# Airflow.net
KiCad netlist of a schematic drawn in EAGLE
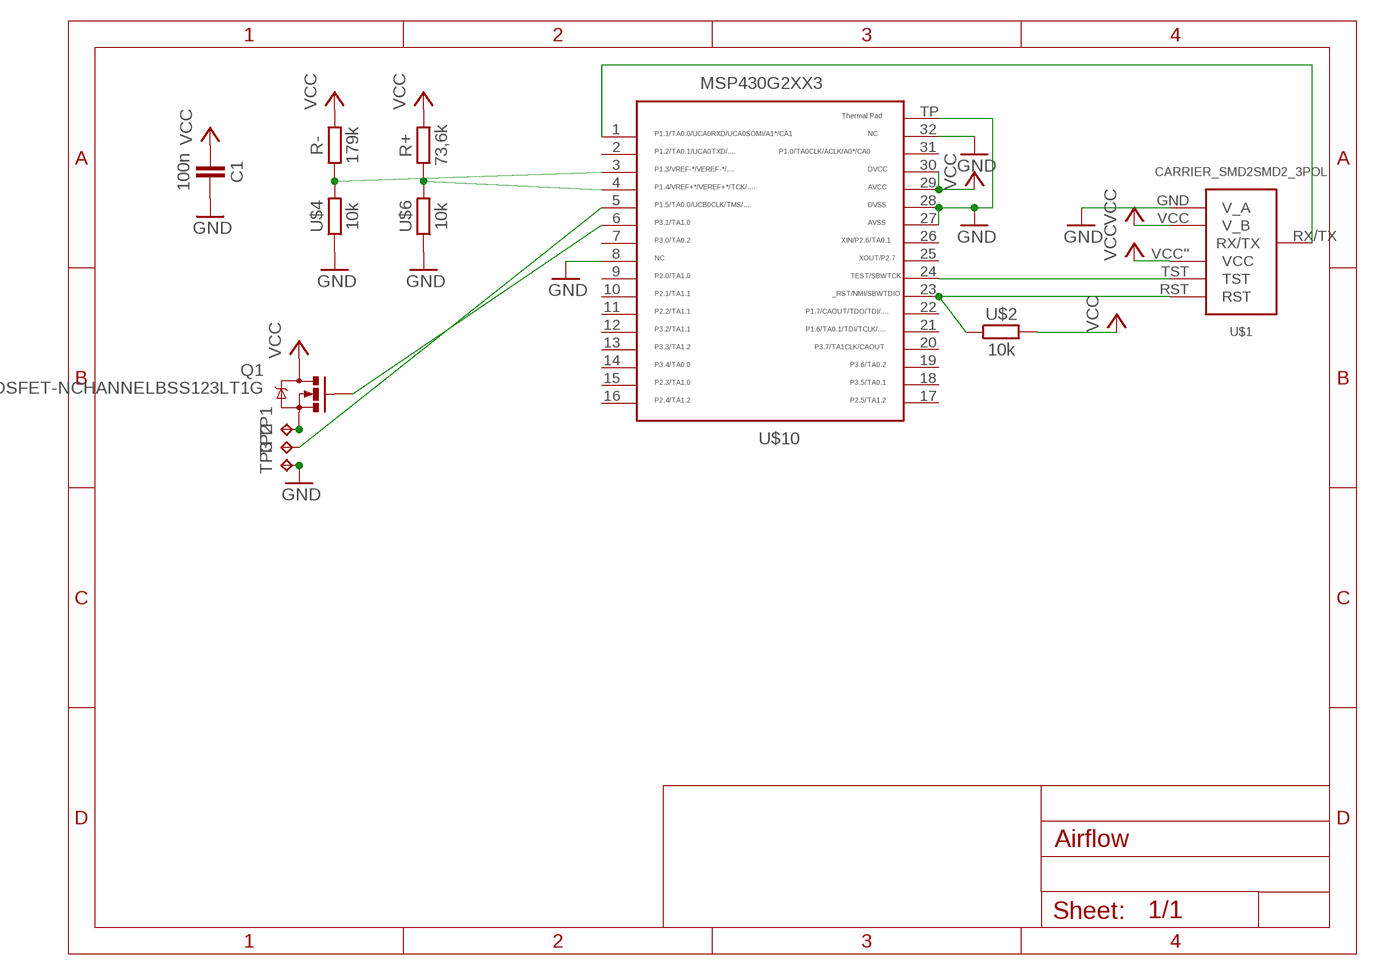
[diagram p0: schematic, sheet 1]

(export (version "E")
  (design (tool "Eeschema 10.0.6"))
  (components
    (comp (ref "C1")
      (value "100n")
      (footprint "eagle-import:603")
      (libsource (lib "eagle-import") (part "CAPACITOR"))
    )
    (comp (ref "Q1")
      (value "MOSFET-NCHANNELBSS123LT1G")
      (footprint "eagle-import:SOT23-3")
      (libsource (lib "eagle-import") (part "MOSFET-NCHANNELBSS123LT1G"))
    )
    (comp (ref "R+")
      (value "73,6k")
      (footprint "eagle-import:603")
      (libsource (lib "eagle-import") (part "RESISTOR0603"))
    )
    (comp (ref "R-")
      (value "179k")
      (footprint "eagle-import:603")
      (libsource (lib "eagle-import") (part "RESISTOR0603"))
    )
    (comp (ref "TP1")
      (value "TPTP18SQ")
      (footprint "eagle-import:TP18SQ")
      (libsource (lib "eagle-import") (part "TPTP18SQ"))
    )
    (comp (ref "TP2")
      (value "TPTP18SQ")
      (footprint "eagle-import:TP18SQ")
      (libsource (lib "eagle-import") (part "TPTP18SQ"))
    )
    (comp (ref "TP3")
      (value "TPTP18SQ")
      (footprint "eagle-import:TP18SQ")
      (libsource (lib "eagle-import") (part "TPTP18SQ"))
    )
    (comp (ref "U$1")
      (value "CARRIER_SMD2SMD2_3POL")
      (footprint "eagle-import:CARRIER_SMD2_3POL")
      (libsource (lib "eagle-import") (part "CARRIER_SMD2SMD2_3POL"))
    )
    (comp (ref "U$2")
      (value "10k")
      (footprint "eagle-import:603")
      (libsource (lib "eagle-import") (part "RESISTOR0603"))
    )
    (comp (ref "U$4")
      (value "10k")
      (footprint "eagle-import:603")
      (libsource (lib "eagle-import") (part "RESISTOR0603"))
    )
    (comp (ref "U$6")
      (value "10k")
      (footprint "eagle-import:603")
      (libsource (lib "eagle-import") (part "RESISTOR0603"))
    )
    (comp (ref "U$10")
      (value "MSP430G2553")
      (footprint "eagle-import:QFN32")
      (libsource (lib "eagle-import") (part "MSP430G2553"))
    )
  )
  (nets
    (net (code "1") (name "GND") (class "Default")
      (node (ref "C1") (pin "2") (pinfunction "2_2") (pintype "passive"))
      (node (ref "TP3") (pin "TP") (pinfunction "TP_TP") (pintype "input"))
      (node (ref "U$1") (pin "GND") (pinfunction "V_A_GND") (pintype "bidirectional"))
      (node (ref "U$10") (pin "27") (pinfunction "27_27") (pintype "bidirectional"))
      (node (ref "U$10") (pin "28") (pinfunction "28_28") (pintype "bidirectional"))
      (node (ref "U$10") (pin "32") (pinfunction "32_32") (pintype "bidirectional"))
      (node (ref "U$10") (pin "8") (pinfunction "8_8") (pintype "bidirectional"))
      (node (ref "U$10") (pin "TP") (pinfunction "TP_TP") (pintype "bidirectional"))
      (node (ref "U$4") (pin "1") (pinfunction "1_1") (pintype "passive"))
      (node (ref "U$6") (pin "1") (pinfunction "1_1") (pintype "passive"))
    )
    (net (code "2") (name "Net-(Q1-G)") (class "Default")
      (node (ref "Q1") (pin "1") (pinfunction "G_1") (pintype "passive"))
      (node (ref "U$10") (pin "6") (pinfunction "6_6") (pintype "bidirectional"))
    )
    (net (code "3") (name "Net-(Q1-S)") (class "Default")
      (node (ref "Q1") (pin "2") (pinfunction "S_2") (pintype "passive"))
      (node (ref "TP1") (pin "TP") (pinfunction "TP_TP") (pintype "input"))
    )
    (net (code "4") (name "Net-(R+-Pad1)") (class "Default")
      (node (ref "R+") (pin "1") (pinfunction "1_1") (pintype "passive"))
      (node (ref "U$10") (pin "4") (pinfunction "4_4") (pintype "bidirectional"))
      (node (ref "U$6") (pin "2") (pinfunction "2_2") (pintype "passive"))
    )
    (net (code "5") (name "Net-(R--Pad1)") (class "Default")
      (node (ref "R-") (pin "1") (pinfunction "1_1") (pintype "passive"))
      (node (ref "U$10") (pin "3") (pinfunction "3_3") (pintype "bidirectional"))
      (node (ref "U$4") (pin "2") (pinfunction "2_2") (pintype "passive"))
    )
    (net (code "6") (name "Net-(TP2-PadTP)") (class "Default")
      (node (ref "TP2") (pin "TP") (pinfunction "TP_TP") (pintype "input"))
      (node (ref "U$10") (pin "5") (pinfunction "5_5") (pintype "bidirectional"))
    )
    (net (code "7") (name "Net-(U$1-PadRST)") (class "Default")
      (node (ref "U$1") (pin "RST") (pinfunction "RST_RST") (pintype "bidirectional"))
      (node (ref "U$10") (pin "23") (pinfunction "23_23") (pintype "bidirectional"))
      (node (ref "U$2") (pin "1") (pinfunction "1_1") (pintype "passive"))
    )
    (net (code "8") (name "Net-(U$1-PadRX{slash}TX)") (class "Default")
      (node (ref "U$1") (pin "RX/TX") (pinfunction "RX/TX_RX/TX") (pintype "bidirectional"))
      (node (ref "U$10") (pin "1") (pinfunction "1_1") (pintype "bidirectional"))
    )
    (net (code "9") (name "Net-(U$1-PadTST)") (class "Default")
      (node (ref "U$1") (pin "TST") (pinfunction "TST_TST") (pintype "bidirectional"))
      (node (ref "U$10") (pin "24") (pinfunction "24_24") (pintype "bidirectional"))
    )
    (net (code "10") (name "VCC") (class "Default")
      (node (ref "C1") (pin "1") (pinfunction "1_1") (pintype "passive"))
      (node (ref "Q1") (pin "3") (pinfunction "D_3") (pintype "passive"))
      (node (ref "R+") (pin "2") (pinfunction "2_2") (pintype "passive"))
      (node (ref "R-") (pin "2") (pinfunction "2_2") (pintype "passive"))
      (node (ref "U$1") (pin "VCC") (pinfunction "V_B_VCC") (pintype "bidirectional"))
      (node (ref "U$1") (pin "VCC''") (pinfunction "VCC_VCC''") (pintype "bidirectional"))
      (node (ref "U$10") (pin "29") (pinfunction "29_29") (pintype "bidirectional"))
      (node (ref "U$10") (pin "30") (pinfunction "30_30") (pintype "bidirectional"))
      (node (ref "U$2") (pin "2") (pinfunction "2_2") (pintype "passive"))
    )
    (net (code "11") (name "unconnected-(U$10-Pad2)") (class "Default")
      (node (ref "U$10") (pin "2") (pinfunction "2_2") (pintype "bidirectional"))
    )
    (net (code "12") (name "unconnected-(U$10-Pad7)") (class "Default")
      (node (ref "U$10") (pin "7") (pinfunction "7_7") (pintype "bidirectional"))
    )
    (net (code "13") (name "unconnected-(U$10-Pad9)") (class "Default")
      (node (ref "U$10") (pin "9") (pinfunction "9_9") (pintype "bidirectional"))
    )
    (net (code "14") (name "unconnected-(U$10-Pad10)") (class "Default")
      (node (ref "U$10") (pin "10") (pinfunction "10_10") (pintype "bidirectional"))
    )
    (net (code "15") (name "unconnected-(U$10-Pad11)") (class "Default")
      (node (ref "U$10") (pin "11") (pinfunction "11_11") (pintype "bidirectional"))
    )
    (net (code "16") (name "unconnected-(U$10-Pad12)") (class "Default")
      (node (ref "U$10") (pin "12") (pinfunction "12_12") (pintype "bidirectional"))
    )
    (net (code "17") (name "unconnected-(U$10-Pad13)") (class "Default")
      (node (ref "U$10") (pin "13") (pinfunction "13_13") (pintype "bidirectional"))
    )
    (net (code "18") (name "unconnected-(U$10-Pad14)") (class "Default")
      (node (ref "U$10") (pin "14") (pinfunction "14_14") (pintype "bidirectional"))
    )
    (net (code "19") (name "unconnected-(U$10-Pad15)") (class "Default")
      (node (ref "U$10") (pin "15") (pinfunction "15_15") (pintype "bidirectional"))
    )
    (net (code "20") (name "unconnected-(U$10-Pad16)") (class "Default")
      (node (ref "U$10") (pin "16") (pinfunction "16_16") (pintype "bidirectional"))
    )
    (net (code "21") (name "unconnected-(U$10-Pad17)") (class "Default")
      (node (ref "U$10") (pin "17") (pinfunction "17_17") (pintype "bidirectional"))
    )
    (net (code "22") (name "unconnected-(U$10-Pad18)") (class "Default")
      (node (ref "U$10") (pin "18") (pinfunction "18_18") (pintype "bidirectional"))
    )
    (net (code "23") (name "unconnected-(U$10-Pad19)") (class "Default")
      (node (ref "U$10") (pin "19") (pinfunction "19_19") (pintype "bidirectional"))
    )
    (net (code "24") (name "unconnected-(U$10-Pad20)") (class "Default")
      (node (ref "U$10") (pin "20") (pinfunction "20_20") (pintype "bidirectional"))
    )
    (net (code "25") (name "unconnected-(U$10-Pad21)") (class "Default")
      (node (ref "U$10") (pin "21") (pinfunction "21_21") (pintype "bidirectional"))
    )
    (net (code "26") (name "unconnected-(U$10-Pad22)") (class "Default")
      (node (ref "U$10") (pin "22") (pinfunction "22_22") (pintype "bidirectional"))
    )
    (net (code "27") (name "unconnected-(U$10-Pad25)") (class "Default")
      (node (ref "U$10") (pin "25") (pinfunction "25_25") (pintype "bidirectional"))
    )
    (net (code "28") (name "unconnected-(U$10-Pad26)") (class "Default")
      (node (ref "U$10") (pin "26") (pinfunction "26_26") (pintype "bidirectional"))
    )
    (net (code "29") (name "unconnected-(U$10-Pad31)") (class "Default")
      (node (ref "U$10") (pin "31") (pinfunction "31_31") (pintype "bidirectional"))
    )
  )
)
